# RH009_1.net
KiCad netlist of a schematic drawn in EAGLE
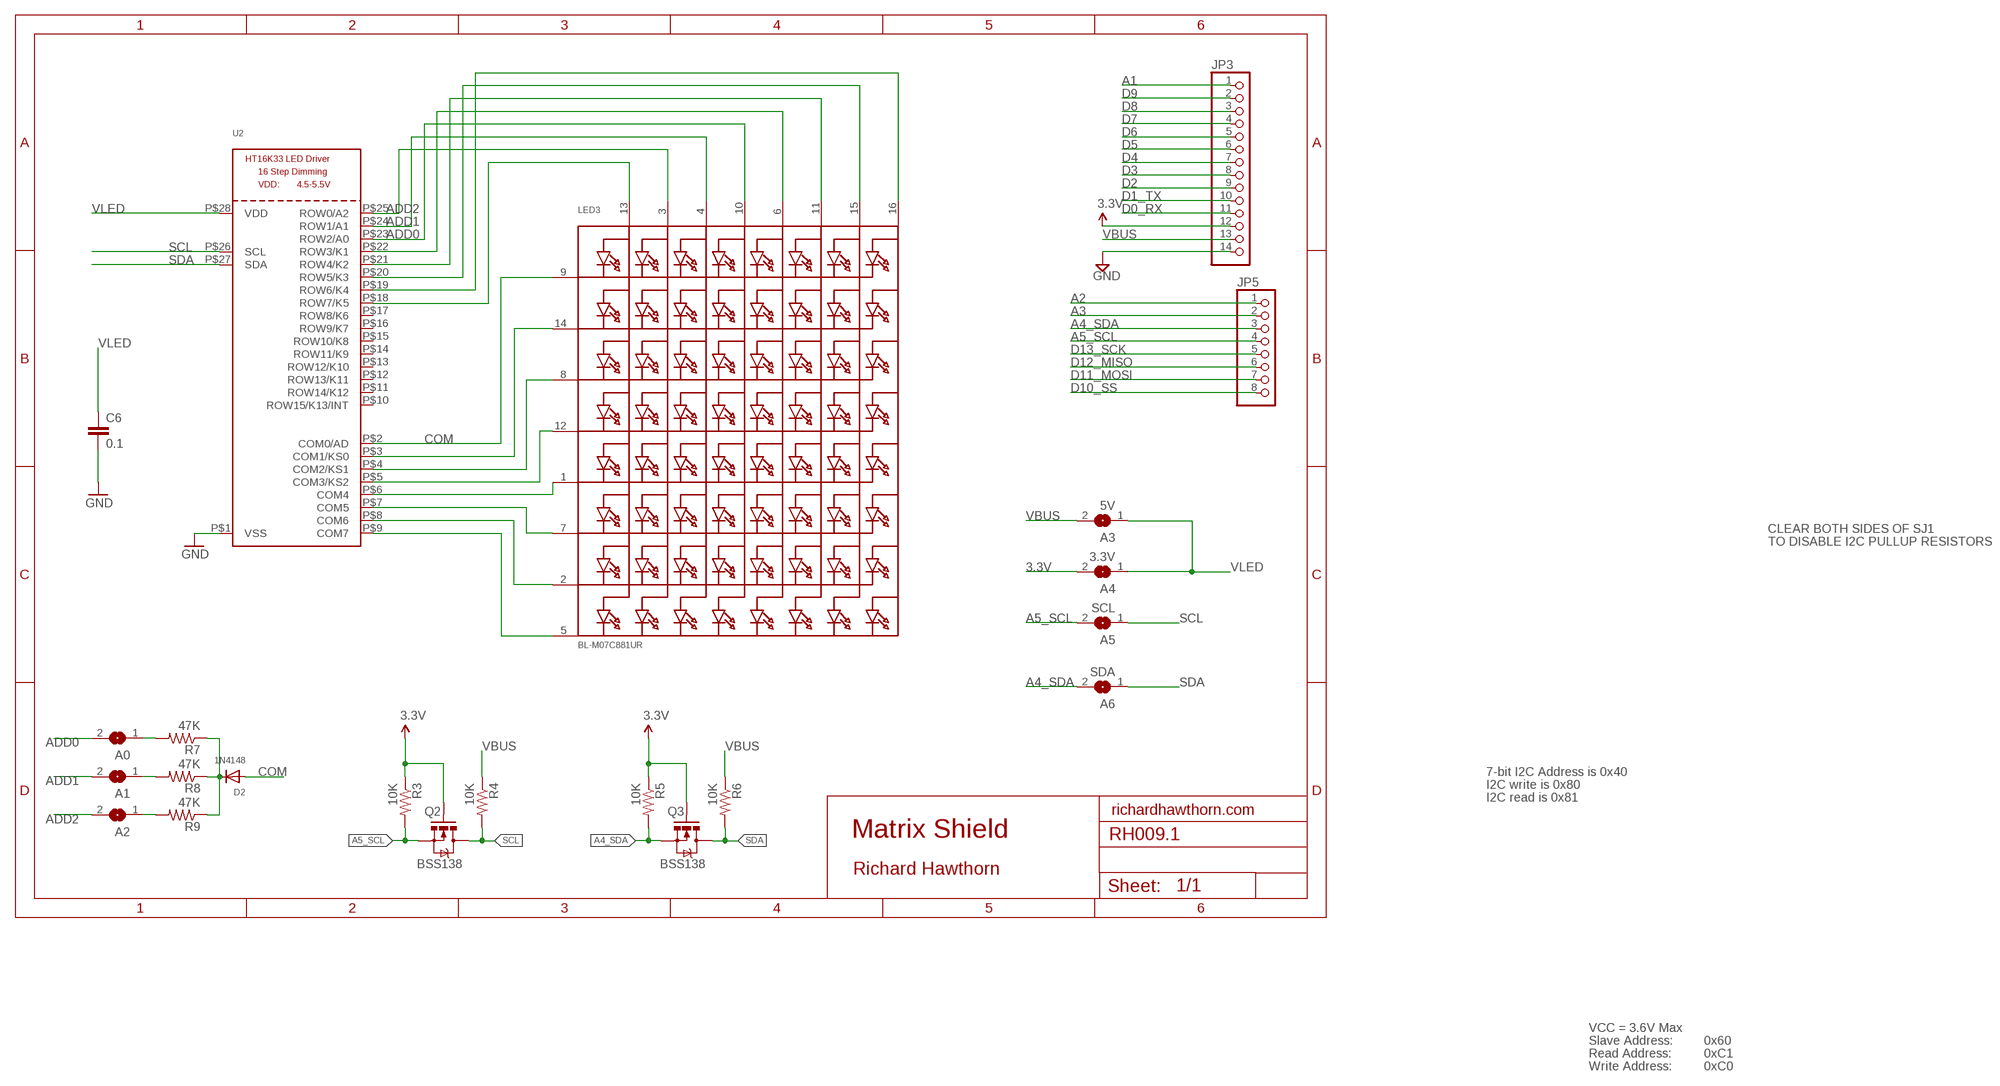
[diagram p0: schematic, sheet 1]

(export (version "E")
  (design (tool "Eeschema 10.0.6"))
  (components
    (comp (ref "A0")
      (value "SOLDERJUMPERREFLOW_NOPASTE")
      (footprint "eagle-import:SOLDERJUMPER_REFLOW_NOPASTE")
      (libsource (lib "eagle-import") (part "SOLDERJUMPERREFLOW_NOPASTE"))
    )
    (comp (ref "A1")
      (value "SOLDERJUMPERREFLOW_NOPASTE")
      (footprint "eagle-import:SOLDERJUMPER_REFLOW_NOPASTE")
      (libsource (lib "eagle-import") (part "SOLDERJUMPERREFLOW_NOPASTE"))
    )
    (comp (ref "A2")
      (value "SOLDERJUMPERREFLOW_NOPASTE")
      (footprint "eagle-import:SOLDERJUMPER_REFLOW_NOPASTE")
      (libsource (lib "eagle-import") (part "SOLDERJUMPERREFLOW_NOPASTE"))
    )
    (comp (ref "A3")
      (value "5V")
      (footprint "eagle-import:SOLDERJUMPER_REFLOW_NOPASTE")
      (libsource (lib "eagle-import") (part "SOLDERJUMPERREFLOW_NOPASTE"))
    )
    (comp (ref "A4")
      (value "3.3V")
      (footprint "eagle-import:SOLDERJUMPER_REFLOW_NOPASTE")
      (libsource (lib "eagle-import") (part "SOLDERJUMPERREFLOW_NOPASTE"))
    )
    (comp (ref "A5")
      (value "SCL")
      (footprint "eagle-import:SOLDERJUMPER_REFLOW_NOPASTE")
      (libsource (lib "eagle-import") (part "SOLDERJUMPERREFLOW_NOPASTE"))
    )
    (comp (ref "A6")
      (value "SDA")
      (footprint "eagle-import:SOLDERJUMPER_REFLOW_NOPASTE")
      (libsource (lib "eagle-import") (part "SOLDERJUMPERREFLOW_NOPASTE"))
    )
    (comp (ref "C6")
      (value "0.1")
      (footprint "eagle-import:0603-CAP")
      (libsource (lib "eagle-import") (part "CAP0603-CAP"))
    )
    (comp (ref "D2")
      (value "1N4148")
      (footprint "eagle-import:SOD-323F")
      (libsource (lib "eagle-import") (part "DIODESOD-323F"))
    )
    (comp (ref "JP3")
      (value "PINHD-1X14")
      (footprint "eagle-import:1X14")
      (libsource (lib "eagle-import") (part "PINHD-1X14"))
    )
    (comp (ref "JP5")
      (value "PINHD-1X8")
      (footprint "eagle-import:1X08")
      (libsource (lib "eagle-import") (part "PINHD-1X8"))
    )
    (comp (ref "LED3")
      (value "BL-M07C881UR")
      (footprint "eagle-import:SEGMENT_BL-M12A881UR")
      (libsource (lib "eagle-import") (part "DISP_SEGMENT_8X8_ROWCATHODEM12A881UR"))
    )
    (comp (ref "Q2")
      (value "BSS138")
      (footprint "eagle-import:SOT23-3")
      (libsource (lib "eagle-import") (part "MOSFET-NCHANNELSMD"))
    )
    (comp (ref "Q3")
      (value "BSS138")
      (footprint "eagle-import:SOT23-3")
      (libsource (lib "eagle-import") (part "MOSFET-NCHANNELSMD"))
    )
    (comp (ref "R3")
      (value "10K")
      (footprint "eagle-import:0603-RES")
      (libsource (lib "eagle-import") (part "RESISTOR0603-RES"))
    )
    (comp (ref "R4")
      (value "10K")
      (footprint "eagle-import:0603-RES")
      (libsource (lib "eagle-import") (part "RESISTOR0603-RES"))
    )
    (comp (ref "R5")
      (value "10K")
      (footprint "eagle-import:0603-RES")
      (libsource (lib "eagle-import") (part "RESISTOR0603-RES"))
    )
    (comp (ref "R6")
      (value "10K")
      (footprint "eagle-import:0603-RES")
      (libsource (lib "eagle-import") (part "RESISTOR0603-RES"))
    )
    (comp (ref "R7")
      (value "47K")
      (footprint "eagle-import:R0805")
      (libsource (lib "eagle-import") (part "R-US_R0805"))
    )
    (comp (ref "R8")
      (value "47K")
      (footprint "eagle-import:R0805")
      (libsource (lib "eagle-import") (part "R-US_R0805"))
    )
    (comp (ref "R9")
      (value "47K")
      (footprint "eagle-import:R0805")
      (libsource (lib "eagle-import") (part "R-US_R0805"))
    )
    (comp (ref "U2")
      (value "HT16K33_SOP28")
      (footprint "eagle-import:SOP28_300MIL")
      (libsource (lib "eagle-import") (part "HT16K33_SOP28"))
    )
  )
  (nets
    (net (code "1") (name "/A1") (class "Default")
      (node (ref "JP3") (pin "1") (pinfunction "1_1") (pintype "passive"))
    )
    (net (code "2") (name "/A2") (class "Default")
      (node (ref "JP5") (pin "1") (pinfunction "1_1") (pintype "passive"))
    )
    (net (code "3") (name "/A3") (class "Default")
      (node (ref "JP5") (pin "2") (pinfunction "2_2") (pintype "passive"))
    )
    (net (code "4") (name "/ADD0") (class "Default")
      (node (ref "A0") (pin "2") (pinfunction "2_2") (pintype "passive"))
      (node (ref "LED3") (pin "10") (pinfunction "A4_10") (pintype "bidirectional"))
      (node (ref "U2") (pin "P$23") (pinfunction "ROW2/A0_P$23") (pintype "bidirectional"))
    )
    (net (code "5") (name "/ADD1") (class "Default")
      (node (ref "A1") (pin "2") (pinfunction "2_2") (pintype "passive"))
      (node (ref "LED3") (pin "4") (pinfunction "A3_4") (pintype "bidirectional"))
      (node (ref "U2") (pin "P$24") (pinfunction "ROW1/A1_P$24") (pintype "bidirectional"))
    )
    (net (code "6") (name "/ADD2") (class "Default")
      (node (ref "A2") (pin "2") (pinfunction "2_2") (pintype "passive"))
      (node (ref "LED3") (pin "3") (pinfunction "A2_3") (pintype "bidirectional"))
      (node (ref "U2") (pin "P$25") (pinfunction "ROW0/A2_P$25") (pintype "bidirectional"))
    )
    (net (code "7") (name "/COM") (class "Default")
      (node (ref "D2") (pin "A") (pinfunction "A_A") (pintype "passive"))
      (node (ref "LED3") (pin "9") (pinfunction "K1_9") (pintype "bidirectional"))
      (node (ref "U2") (pin "P$2") (pinfunction "COM0/AD_P$2") (pintype "bidirectional"))
    )
    (net (code "8") (name "/D0_RX") (class "Default")
      (node (ref "JP3") (pin "11") (pinfunction "11_11") (pintype "passive"))
    )
    (net (code "9") (name "/D1_TX") (class "Default")
      (node (ref "JP3") (pin "10") (pinfunction "10_10") (pintype "passive"))
    )
    (net (code "10") (name "/D2") (class "Default")
      (node (ref "JP3") (pin "9") (pinfunction "9_9") (pintype "passive"))
    )
    (net (code "11") (name "/D3") (class "Default")
      (node (ref "JP3") (pin "8") (pinfunction "8_8") (pintype "passive"))
    )
    (net (code "12") (name "/D4") (class "Default")
      (node (ref "JP3") (pin "7") (pinfunction "7_7") (pintype "passive"))
    )
    (net (code "13") (name "/D5") (class "Default")
      (node (ref "JP3") (pin "6") (pinfunction "6_6") (pintype "passive"))
    )
    (net (code "14") (name "/D6") (class "Default")
      (node (ref "JP3") (pin "5") (pinfunction "5_5") (pintype "passive"))
    )
    (net (code "15") (name "/D7") (class "Default")
      (node (ref "JP3") (pin "4") (pinfunction "4_4") (pintype "passive"))
    )
    (net (code "16") (name "/D8") (class "Default")
      (node (ref "JP3") (pin "3") (pinfunction "3_3") (pintype "passive"))
    )
    (net (code "17") (name "/D9") (class "Default")
      (node (ref "JP3") (pin "2") (pinfunction "2_2") (pintype "passive"))
    )
    (net (code "18") (name "/D10_SS") (class "Default")
      (node (ref "JP5") (pin "8") (pinfunction "8_8") (pintype "passive"))
    )
    (net (code "19") (name "/D11_MOSI") (class "Default")
      (node (ref "JP5") (pin "7") (pinfunction "7_7") (pintype "passive"))
    )
    (net (code "20") (name "/D12_MISO") (class "Default")
      (node (ref "JP5") (pin "6") (pinfunction "6_6") (pintype "passive"))
    )
    (net (code "21") (name "/D13_SCK") (class "Default")
      (node (ref "JP5") (pin "5") (pinfunction "5_5") (pintype "passive"))
    )
    (net (code "22") (name "/VBUS") (class "Default")
      (node (ref "A3") (pin "2") (pinfunction "2_2") (pintype "passive"))
      (node (ref "JP3") (pin "13") (pinfunction "13_13") (pintype "passive"))
      (node (ref "R4") (pin "1") (pinfunction "1_1") (pintype "passive"))
      (node (ref "R6") (pin "1") (pinfunction "1_1") (pintype "passive"))
    )
    (net (code "23") (name "/VLED") (class "Default")
      (node (ref "A3") (pin "1") (pinfunction "1_1") (pintype "passive"))
      (node (ref "A4") (pin "1") (pinfunction "1_1") (pintype "passive"))
      (node (ref "C6") (pin "1") (pinfunction "1_1") (pintype "passive"))
      (node (ref "U2") (pin "P$28") (pinfunction "VDD_P$28") (pintype "bidirectional"))
    )
    (net (code "24") (name "3.3V") (class "Default")
      (node (ref "A4") (pin "2") (pinfunction "2_2") (pintype "passive"))
      (node (ref "JP3") (pin "12") (pinfunction "12_12") (pintype "passive"))
      (node (ref "Q2") (pin "1") (pinfunction "G_1") (pintype "passive"))
      (node (ref "Q3") (pin "1") (pinfunction "G_1") (pintype "passive"))
      (node (ref "R3") (pin "1") (pinfunction "1_1") (pintype "passive"))
      (node (ref "R5") (pin "1") (pinfunction "1_1") (pintype "passive"))
    )
    (net (code "25") (name "A4_SDA") (class "Default")
      (node (ref "A6") (pin "2") (pinfunction "2_2") (pintype "passive"))
      (node (ref "JP5") (pin "3") (pinfunction "3_3") (pintype "passive"))
      (node (ref "Q3") (pin "2") (pinfunction "S_2") (pintype "passive"))
      (node (ref "R5") (pin "2") (pinfunction "2_2") (pintype "passive"))
    )
    (net (code "26") (name "A5_SCL") (class "Default")
      (node (ref "A5") (pin "2") (pinfunction "2_2") (pintype "passive"))
      (node (ref "JP5") (pin "4") (pinfunction "4_4") (pintype "passive"))
      (node (ref "Q2") (pin "2") (pinfunction "S_2") (pintype "passive"))
      (node (ref "R3") (pin "2") (pinfunction "2_2") (pintype "passive"))
    )
    (net (code "27") (name "GND") (class "Default")
      (node (ref "C6") (pin "2") (pinfunction "2_2") (pintype "passive"))
      (node (ref "JP3") (pin "14") (pinfunction "14_14") (pintype "passive"))
      (node (ref "U2") (pin "P$1") (pinfunction "VSS_P$1") (pintype "bidirectional"))
    )
    (net (code "28") (name "Net-(A0-Pad1)") (class "Default")
      (node (ref "A0") (pin "1") (pinfunction "1_1") (pintype "passive"))
      (node (ref "R7") (pin "2") (pinfunction "2_2") (pintype "passive"))
    )
    (net (code "29") (name "Net-(A1-Pad1)") (class "Default")
      (node (ref "A1") (pin "1") (pinfunction "1_1") (pintype "passive"))
      (node (ref "R8") (pin "2") (pinfunction "2_2") (pintype "passive"))
    )
    (net (code "30") (name "Net-(A2-Pad1)") (class "Default")
      (node (ref "A2") (pin "1") (pinfunction "1_1") (pintype "passive"))
      (node (ref "R9") (pin "2") (pinfunction "2_2") (pintype "passive"))
    )
    (net (code "31") (name "Net-(D2-PadC)") (class "Default")
      (node (ref "D2") (pin "C") (pinfunction "C_C") (pintype "passive"))
      (node (ref "R7") (pin "1") (pinfunction "1_1") (pintype "passive"))
      (node (ref "R8") (pin "1") (pinfunction "1_1") (pintype "passive"))
      (node (ref "R9") (pin "1") (pinfunction "1_1") (pintype "passive"))
    )
    (net (code "32") (name "Net-(LED3-A1)") (class "Default")
      (node (ref "LED3") (pin "13") (pinfunction "A1_13") (pintype "bidirectional"))
      (node (ref "U2") (pin "P$18") (pinfunction "ROW7/K5_P$18") (pintype "bidirectional"))
    )
    (net (code "33") (name "Net-(LED3-A5)") (class "Default")
      (node (ref "LED3") (pin "6") (pinfunction "A5_6") (pintype "bidirectional"))
      (node (ref "U2") (pin "P$22") (pinfunction "ROW3/K1_P$22") (pintype "bidirectional"))
    )
    (net (code "34") (name "Net-(LED3-A6)") (class "Default")
      (node (ref "LED3") (pin "11") (pinfunction "A6_11") (pintype "bidirectional"))
      (node (ref "U2") (pin "P$21") (pinfunction "ROW4/K2_P$21") (pintype "bidirectional"))
    )
    (net (code "35") (name "Net-(LED3-A7)") (class "Default")
      (node (ref "LED3") (pin "15") (pinfunction "A7_15") (pintype "bidirectional"))
      (node (ref "U2") (pin "P$20") (pinfunction "ROW5/K3_P$20") (pintype "bidirectional"))
    )
    (net (code "36") (name "Net-(LED3-A8)") (class "Default")
      (node (ref "LED3") (pin "16") (pinfunction "A8_16") (pintype "bidirectional"))
      (node (ref "U2") (pin "P$19") (pinfunction "ROW6/K4_P$19") (pintype "bidirectional"))
    )
    (net (code "37") (name "Net-(LED3-K2)") (class "Default")
      (node (ref "LED3") (pin "14") (pinfunction "K2_14") (pintype "bidirectional"))
      (node (ref "U2") (pin "P$3") (pinfunction "COM1/KS0_P$3") (pintype "bidirectional"))
    )
    (net (code "38") (name "Net-(LED3-K3)") (class "Default")
      (node (ref "LED3") (pin "8") (pinfunction "K3_8") (pintype "bidirectional"))
      (node (ref "U2") (pin "P$4") (pinfunction "COM2/KS1_P$4") (pintype "bidirectional"))
    )
    (net (code "39") (name "Net-(LED3-K4)") (class "Default")
      (node (ref "LED3") (pin "12") (pinfunction "K4_12") (pintype "bidirectional"))
      (node (ref "U2") (pin "P$5") (pinfunction "COM3/KS2_P$5") (pintype "bidirectional"))
    )
    (net (code "40") (name "Net-(LED3-K5)") (class "Default")
      (node (ref "LED3") (pin "1") (pinfunction "K5_1") (pintype "bidirectional"))
      (node (ref "U2") (pin "P$6") (pinfunction "COM4_P$6") (pintype "bidirectional"))
    )
    (net (code "41") (name "Net-(LED3-K6)") (class "Default")
      (node (ref "LED3") (pin "7") (pinfunction "K6_7") (pintype "bidirectional"))
      (node (ref "U2") (pin "P$7") (pinfunction "COM5_P$7") (pintype "bidirectional"))
    )
    (net (code "42") (name "Net-(LED3-K7)") (class "Default")
      (node (ref "LED3") (pin "2") (pinfunction "K7_2") (pintype "bidirectional"))
      (node (ref "U2") (pin "P$8") (pinfunction "COM6_P$8") (pintype "bidirectional"))
    )
    (net (code "43") (name "Net-(LED3-K8)") (class "Default")
      (node (ref "LED3") (pin "5") (pinfunction "K8_5") (pintype "bidirectional"))
      (node (ref "U2") (pin "P$9") (pinfunction "COM7_P$9") (pintype "bidirectional"))
    )
    (net (code "44") (name "SCL") (class "Default")
      (node (ref "A5") (pin "1") (pinfunction "1_1") (pintype "passive"))
      (node (ref "Q2") (pin "3") (pinfunction "D_3") (pintype "passive"))
      (node (ref "R4") (pin "2") (pinfunction "2_2") (pintype "passive"))
      (node (ref "U2") (pin "P$26") (pinfunction "SCL_P$26") (pintype "bidirectional"))
    )
    (net (code "45") (name "SDA") (class "Default")
      (node (ref "A6") (pin "1") (pinfunction "1_1") (pintype "passive"))
      (node (ref "Q3") (pin "3") (pinfunction "D_3") (pintype "passive"))
      (node (ref "R6") (pin "2") (pinfunction "2_2") (pintype "passive"))
      (node (ref "U2") (pin "P$27") (pinfunction "SDA_P$27") (pintype "bidirectional"))
    )
    (net (code "46") (name "unconnected-(U2-ROW8{slash}K6-PadP$17)") (class "Default")
      (node (ref "U2") (pin "P$17") (pinfunction "ROW8/K6_P$17") (pintype "bidirectional"))
    )
    (net (code "47") (name "unconnected-(U2-ROW9{slash}K7-PadP$16)") (class "Default")
      (node (ref "U2") (pin "P$16") (pinfunction "ROW9/K7_P$16") (pintype "bidirectional"))
    )
    (net (code "48") (name "unconnected-(U2-ROW10{slash}K8-PadP$15)") (class "Default")
      (node (ref "U2") (pin "P$15") (pinfunction "ROW10/K8_P$15") (pintype "bidirectional"))
    )
    (net (code "49") (name "unconnected-(U2-ROW11{slash}K9-PadP$14)") (class "Default")
      (node (ref "U2") (pin "P$14") (pinfunction "ROW11/K9_P$14") (pintype "bidirectional"))
    )
    (net (code "50") (name "unconnected-(U2-ROW12{slash}K10-PadP$13)") (class "Default")
      (node (ref "U2") (pin "P$13") (pinfunction "ROW12/K10_P$13") (pintype "bidirectional"))
    )
    (net (code "51") (name "unconnected-(U2-ROW13{slash}K11-PadP$12)") (class "Default")
      (node (ref "U2") (pin "P$12") (pinfunction "ROW13/K11_P$12") (pintype "bidirectional"))
    )
    (net (code "52") (name "unconnected-(U2-ROW14{slash}K12-PadP$11)") (class "Default")
      (node (ref "U2") (pin "P$11") (pinfunction "ROW14/K12_P$11") (pintype "bidirectional"))
    )
    (net (code "53") (name "unconnected-(U2-ROW15{slash}K13{slash}INT-PadP$10)") (class "Default")
      (node (ref "U2") (pin "P$10") (pinfunction "ROW15/K13/INT_P$10") (pintype "bidirectional"))
    )
  )
)
